# lab2Schematic.net
KiCad netlist of a schematic drawn in EAGLE
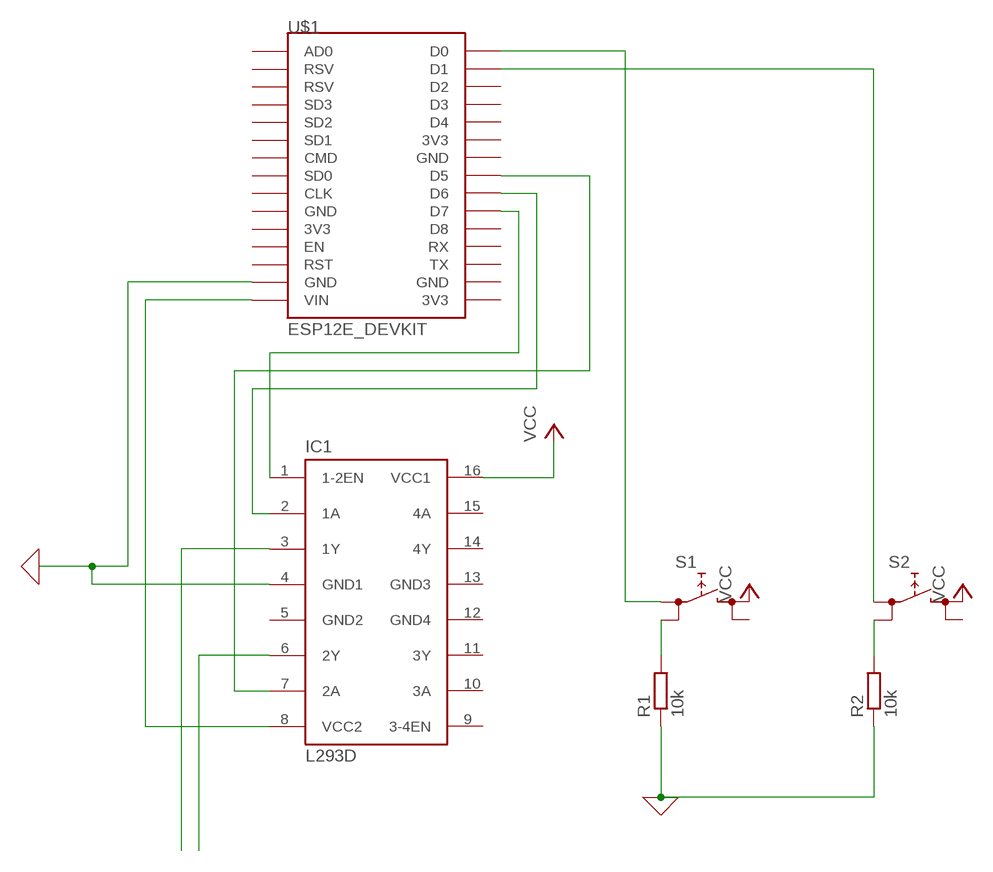
[diagram p0: schematic, sheet 1]

(export (version "E")
  (design (tool "Eeschema 10.0.6"))
  (components
    (comp (ref "IC1")
      (value "L293D")
      (footprint "eagle-import:DIL16")
      (libsource (lib "eagle-import") (part "L293D"))
    )
    (comp (ref "R1")
      (value "10k")
      (footprint "eagle-import:0207_10")
      (libsource (lib "eagle-import") (part "R-EU_0207/10"))
    )
    (comp (ref "R2")
      (value "10k")
      (footprint "eagle-import:0207_10")
      (libsource (lib "eagle-import") (part "R-EU_0207/10"))
    )
    (comp (ref "S1")
      (value "REKN")
      (footprint "eagle-import:REKN")
      (libsource (lib "eagle-import") (part "REKN"))
    )
    (comp (ref "S2")
      (value "REKN")
      (footprint "eagle-import:REKN")
      (libsource (lib "eagle-import") (part "REKN"))
    )
    (comp (ref "U$1")
      (value "ESP12E_DEVKIT")
      (footprint "eagle-import:ESP12E_DEVKIT")
      (libsource (lib "eagle-import") (part "ESP12E_DEVKIT"))
    )
  )
  (nets
    (net (code "1") (name "/GND2") (class "Default")
      (node (ref "IC1") (pin "5") (pinfunction "GND2_5") (pintype "power_in"))
    )
    (net (code "2") (name "/GND3") (class "Default")
      (node (ref "IC1") (pin "13") (pinfunction "GND3_13") (pintype "power_in"))
    )
    (net (code "3") (name "/GND4") (class "Default")
      (node (ref "IC1") (pin "12") (pinfunction "GND4_12") (pintype "power_in"))
    )
    (net (code "4") (name "GND") (class "Default")
      (node (ref "IC1") (pin "4") (pinfunction "GND1_4") (pintype "power_in"))
      (node (ref "R1") (pin "1") (pinfunction "1_1") (pintype "passive"))
      (node (ref "R2") (pin "1") (pinfunction "1_1") (pintype "passive"))
      (node (ref "U$1") (pin "GND@1") (pinfunction "GND_GND@1") (pintype "bidirectional"))
    )
    (net (code "5") (name "Net-(IC1-1-2EN)") (class "Default")
      (node (ref "IC1") (pin "1") (pinfunction "1-2EN_1") (pintype "input"))
      (node (ref "U$1") (pin "D7") (pinfunction "D7_D7") (pintype "bidirectional"))
    )
    (net (code "6") (name "Net-(IC1-1A)") (class "Default")
      (node (ref "IC1") (pin "2") (pinfunction "1A_2") (pintype "input"))
      (node (ref "U$1") (pin "D6") (pinfunction "D6_D6") (pintype "bidirectional"))
    )
    (net (code "7") (name "Net-(IC1-2A)") (class "Default")
      (node (ref "IC1") (pin "7") (pinfunction "2A_7") (pintype "input"))
      (node (ref "U$1") (pin "D5") (pinfunction "D5_D5") (pintype "bidirectional"))
    )
    (net (code "8") (name "Net-(IC1-VCC2)") (class "Default")
      (node (ref "IC1") (pin "8") (pinfunction "VCC2_8") (pintype "power_in"))
      (node (ref "U$1") (pin "VIN") (pinfunction "VIN_VIN") (pintype "bidirectional"))
    )
    (net (code "9") (name "Net-(R1-Pad2)") (class "Default")
      (node (ref "R1") (pin "2") (pinfunction "2_2") (pintype "passive"))
      (node (ref "S1") (pin "0B") (pinfunction "0_0B") (pintype "passive"))
    )
    (net (code "10") (name "Net-(R2-Pad2)") (class "Default")
      (node (ref "R2") (pin "2") (pinfunction "2_2") (pintype "passive"))
      (node (ref "S2") (pin "0B") (pinfunction "0_0B") (pintype "passive"))
    )
    (net (code "11") (name "Net-(S1-0-Pad0A)") (class "Default")
      (node (ref "S1") (pin "0A") (pinfunction "0_0A") (pintype "passive"))
      (node (ref "U$1") (pin "D0") (pinfunction "D0_D0") (pintype "bidirectional"))
    )
    (net (code "12") (name "Net-(S2-0-Pad0A)") (class "Default")
      (node (ref "S2") (pin "0A") (pinfunction "0_0A") (pintype "passive"))
      (node (ref "U$1") (pin "D1") (pinfunction "D1_D1") (pintype "bidirectional"))
    )
    (net (code "13") (name "VCC") (class "Default")
      (node (ref "IC1") (pin "16") (pinfunction "VCC1_16") (pintype "power_in"))
      (node (ref "S1") (pin "1A") (pinfunction "1_1A") (pintype "passive"))
      (node (ref "S2") (pin "1A") (pinfunction "1_1A") (pintype "passive"))
    )
    (net (code "14") (name "unconnected-(IC1-1Y-Pad3)") (class "Default")
      (node (ref "IC1") (pin "3") (pinfunction "1Y_3") (pintype "output"))
    )
    (net (code "15") (name "unconnected-(IC1-2Y-Pad6)") (class "Default")
      (node (ref "IC1") (pin "6") (pinfunction "2Y_6") (pintype "output"))
    )
    (net (code "16") (name "unconnected-(IC1-3-4EN-Pad9)") (class "Default")
      (node (ref "IC1") (pin "9") (pinfunction "3-4EN_9") (pintype "input"))
    )
    (net (code "17") (name "unconnected-(IC1-3A-Pad10)") (class "Default")
      (node (ref "IC1") (pin "10") (pinfunction "3A_10") (pintype "input"))
    )
    (net (code "18") (name "unconnected-(IC1-3Y-Pad11)") (class "Default")
      (node (ref "IC1") (pin "11") (pinfunction "3Y_11") (pintype "output"))
    )
    (net (code "19") (name "unconnected-(IC1-4A-Pad15)") (class "Default")
      (node (ref "IC1") (pin "15") (pinfunction "4A_15") (pintype "input"))
    )
    (net (code "20") (name "unconnected-(IC1-4Y-Pad14)") (class "Default")
      (node (ref "IC1") (pin "14") (pinfunction "4Y_14") (pintype "output"))
    )
    (net (code "21") (name "unconnected-(S1-1-Pad1B)") (class "Default")
      (node (ref "S1") (pin "1B") (pinfunction "1_1B") (pintype "passive"))
    )
    (net (code "22") (name "unconnected-(S2-1-Pad1B)") (class "Default")
      (node (ref "S2") (pin "1B") (pinfunction "1_1B") (pintype "passive"))
    )
    (net (code "23") (name "unconnected-(U$1-3V3-Pad3V3@0)") (class "Default")
      (node (ref "U$1") (pin "3V3@0") (pinfunction "3V3_3V3@0") (pintype "bidirectional"))
    )
    (net (code "24") (name "unconnected-(U$1-3V3-Pad3V3@1)") (class "Default")
      (node (ref "U$1") (pin "3V3@1") (pinfunction "3V3_3V3@1") (pintype "bidirectional"))
    )
    (net (code "25") (name "unconnected-(U$1-3V3-Pad3V3@2)") (class "Default")
      (node (ref "U$1") (pin "3V3@2") (pinfunction "3V3_3V3@2") (pintype "bidirectional"))
    )
    (net (code "26") (name "unconnected-(U$1-GND-PadGND@0)") (class "Default")
      (node (ref "U$1") (pin "GND@0") (pinfunction "GND_GND@0") (pintype "bidirectional"))
    )
    (net (code "27") (name "unconnected-(U$1-GND-PadGND@2)") (class "Default")
      (node (ref "U$1") (pin "GND@2") (pinfunction "GND_GND@2") (pintype "bidirectional"))
    )
    (net (code "28") (name "unconnected-(U$1-GND-PadGND@3)") (class "Default")
      (node (ref "U$1") (pin "GND@3") (pinfunction "GND_GND@3") (pintype "bidirectional"))
    )
    (net (code "29") (name "unconnected-(U$1-PadAD0)") (class "Default")
      (node (ref "U$1") (pin "AD0") (pinfunction "AD0_AD0") (pintype "bidirectional"))
    )
    (net (code "30") (name "unconnected-(U$1-PadCLK)") (class "Default")
      (node (ref "U$1") (pin "CLK") (pinfunction "CLK_CLK") (pintype "bidirectional"))
    )
    (net (code "31") (name "unconnected-(U$1-PadCMD)") (class "Default")
      (node (ref "U$1") (pin "CMD") (pinfunction "CMD_CMD") (pintype "bidirectional"))
    )
    (net (code "32") (name "unconnected-(U$1-PadD2)") (class "Default")
      (node (ref "U$1") (pin "D2") (pinfunction "D2_D2") (pintype "bidirectional"))
    )
    (net (code "33") (name "unconnected-(U$1-PadD3)") (class "Default")
      (node (ref "U$1") (pin "D3") (pinfunction "D3_D3") (pintype "bidirectional"))
    )
    (net (code "34") (name "unconnected-(U$1-PadD4)") (class "Default")
      (node (ref "U$1") (pin "D4") (pinfunction "D4_D4") (pintype "bidirectional"))
    )
    (net (code "35") (name "unconnected-(U$1-PadD8)") (class "Default")
      (node (ref "U$1") (pin "D8") (pinfunction "D8_D8") (pintype "bidirectional"))
    )
    (net (code "36") (name "unconnected-(U$1-PadEN)") (class "Default")
      (node (ref "U$1") (pin "EN") (pinfunction "EN_EN") (pintype "bidirectional"))
    )
    (net (code "37") (name "unconnected-(U$1-PadRST)") (class "Default")
      (node (ref "U$1") (pin "RST") (pinfunction "RST_RST") (pintype "bidirectional"))
    )
    (net (code "38") (name "unconnected-(U$1-PadRX)") (class "Default")
      (node (ref "U$1") (pin "RX") (pinfunction "RX_RX") (pintype "bidirectional"))
    )
    (net (code "39") (name "unconnected-(U$1-PadSD0)") (class "Default")
      (node (ref "U$1") (pin "SD0") (pinfunction "SD0_SD0") (pintype "bidirectional"))
    )
    (net (code "40") (name "unconnected-(U$1-PadSD1)") (class "Default")
      (node (ref "U$1") (pin "SD1") (pinfunction "SD1_SD1") (pintype "bidirectional"))
    )
    (net (code "41") (name "unconnected-(U$1-PadSD2)") (class "Default")
      (node (ref "U$1") (pin "SD2") (pinfunction "SD2_SD2") (pintype "bidirectional"))
    )
    (net (code "42") (name "unconnected-(U$1-PadSD3)") (class "Default")
      (node (ref "U$1") (pin "SD3") (pinfunction "SD3_SD3") (pintype "bidirectional"))
    )
    (net (code "43") (name "unconnected-(U$1-PadTX)") (class "Default")
      (node (ref "U$1") (pin "TX") (pinfunction "TX_TX") (pintype "bidirectional"))
    )
    (net (code "44") (name "unconnected-(U$1-RSV-PadRSV@0)") (class "Default")
      (node (ref "U$1") (pin "RSV@0") (pinfunction "RSV_RSV@0") (pintype "bidirectional"))
    )
    (net (code "45") (name "unconnected-(U$1-RSV-PadRSV@1)") (class "Default")
      (node (ref "U$1") (pin "RSV@1") (pinfunction "RSV_RSV@1") (pintype "bidirectional"))
    )
  )
)
